# v1_0.net
KiCad netlist of a schematic drawn in Altium Designer
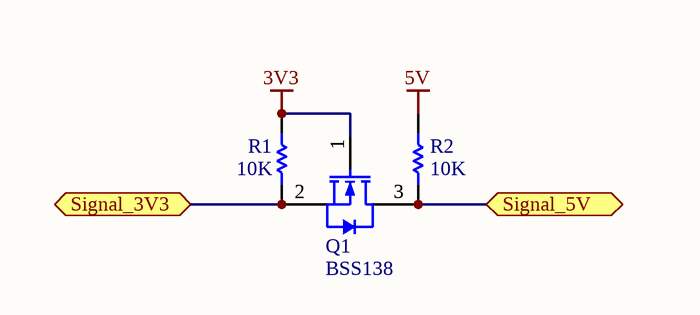
[diagram p0: v1.0.SchDoc]

(export (version "E")
  (design (tool "Eeschema 10.0.6"))
  (components
    (comp (ref "Q1")
      (value "BSS138")
      (footprint "SOT23_3PIN")
      (libsource (lib "General") (part "Transistor_MOSFET_N-Channel_3Type"))
    )
    (comp (ref "R1")
      (value "10K")
      (footprint "SMD_0805")
      (description "Resistor, 1/4W, 5%")
      (libsource (lib "") (part "Resistor_1"))
    )
    (comp (ref "R2")
      (value "10K")
      (footprint "SMD_0805")
      (description "Resistor, 1/4W, 5%")
      (libsource (lib "General") (part "Resistor"))
    )
  )
  (nets
    (net (code "1") (name "/Signal_3V3") (class "Default")
      (node (ref "Q1") (pin "2") (pinfunction "S_2") (pintype "passive"))
      (node (ref "R1") (pin "2") (pinfunction "2_2") (pintype "passive"))
    )
    (net (code "2") (name "/Signal_5V") (class "Default")
      (node (ref "Q1") (pin "3") (pinfunction "D_3") (pintype "passive"))
      (node (ref "R2") (pin "1") (pinfunction "1_1") (pintype "passive"))
    )
    (net (code "3") (name "3V3") (class "Default")
      (node (ref "Q1") (pin "1") (pinfunction "G_1") (pintype "passive"))
      (node (ref "R1") (pin "1") (pinfunction "1_1") (pintype "passive"))
    )
    (net (code "4") (name "5V") (class "Default")
      (node (ref "R2") (pin "2") (pinfunction "2_2") (pintype "passive"))
    )
  )
)
